# ProProject_PetCareSTM32_MiniSTM32_2024-0.net
KiCad netlist of a schematic drawn in EasyEDA Pro
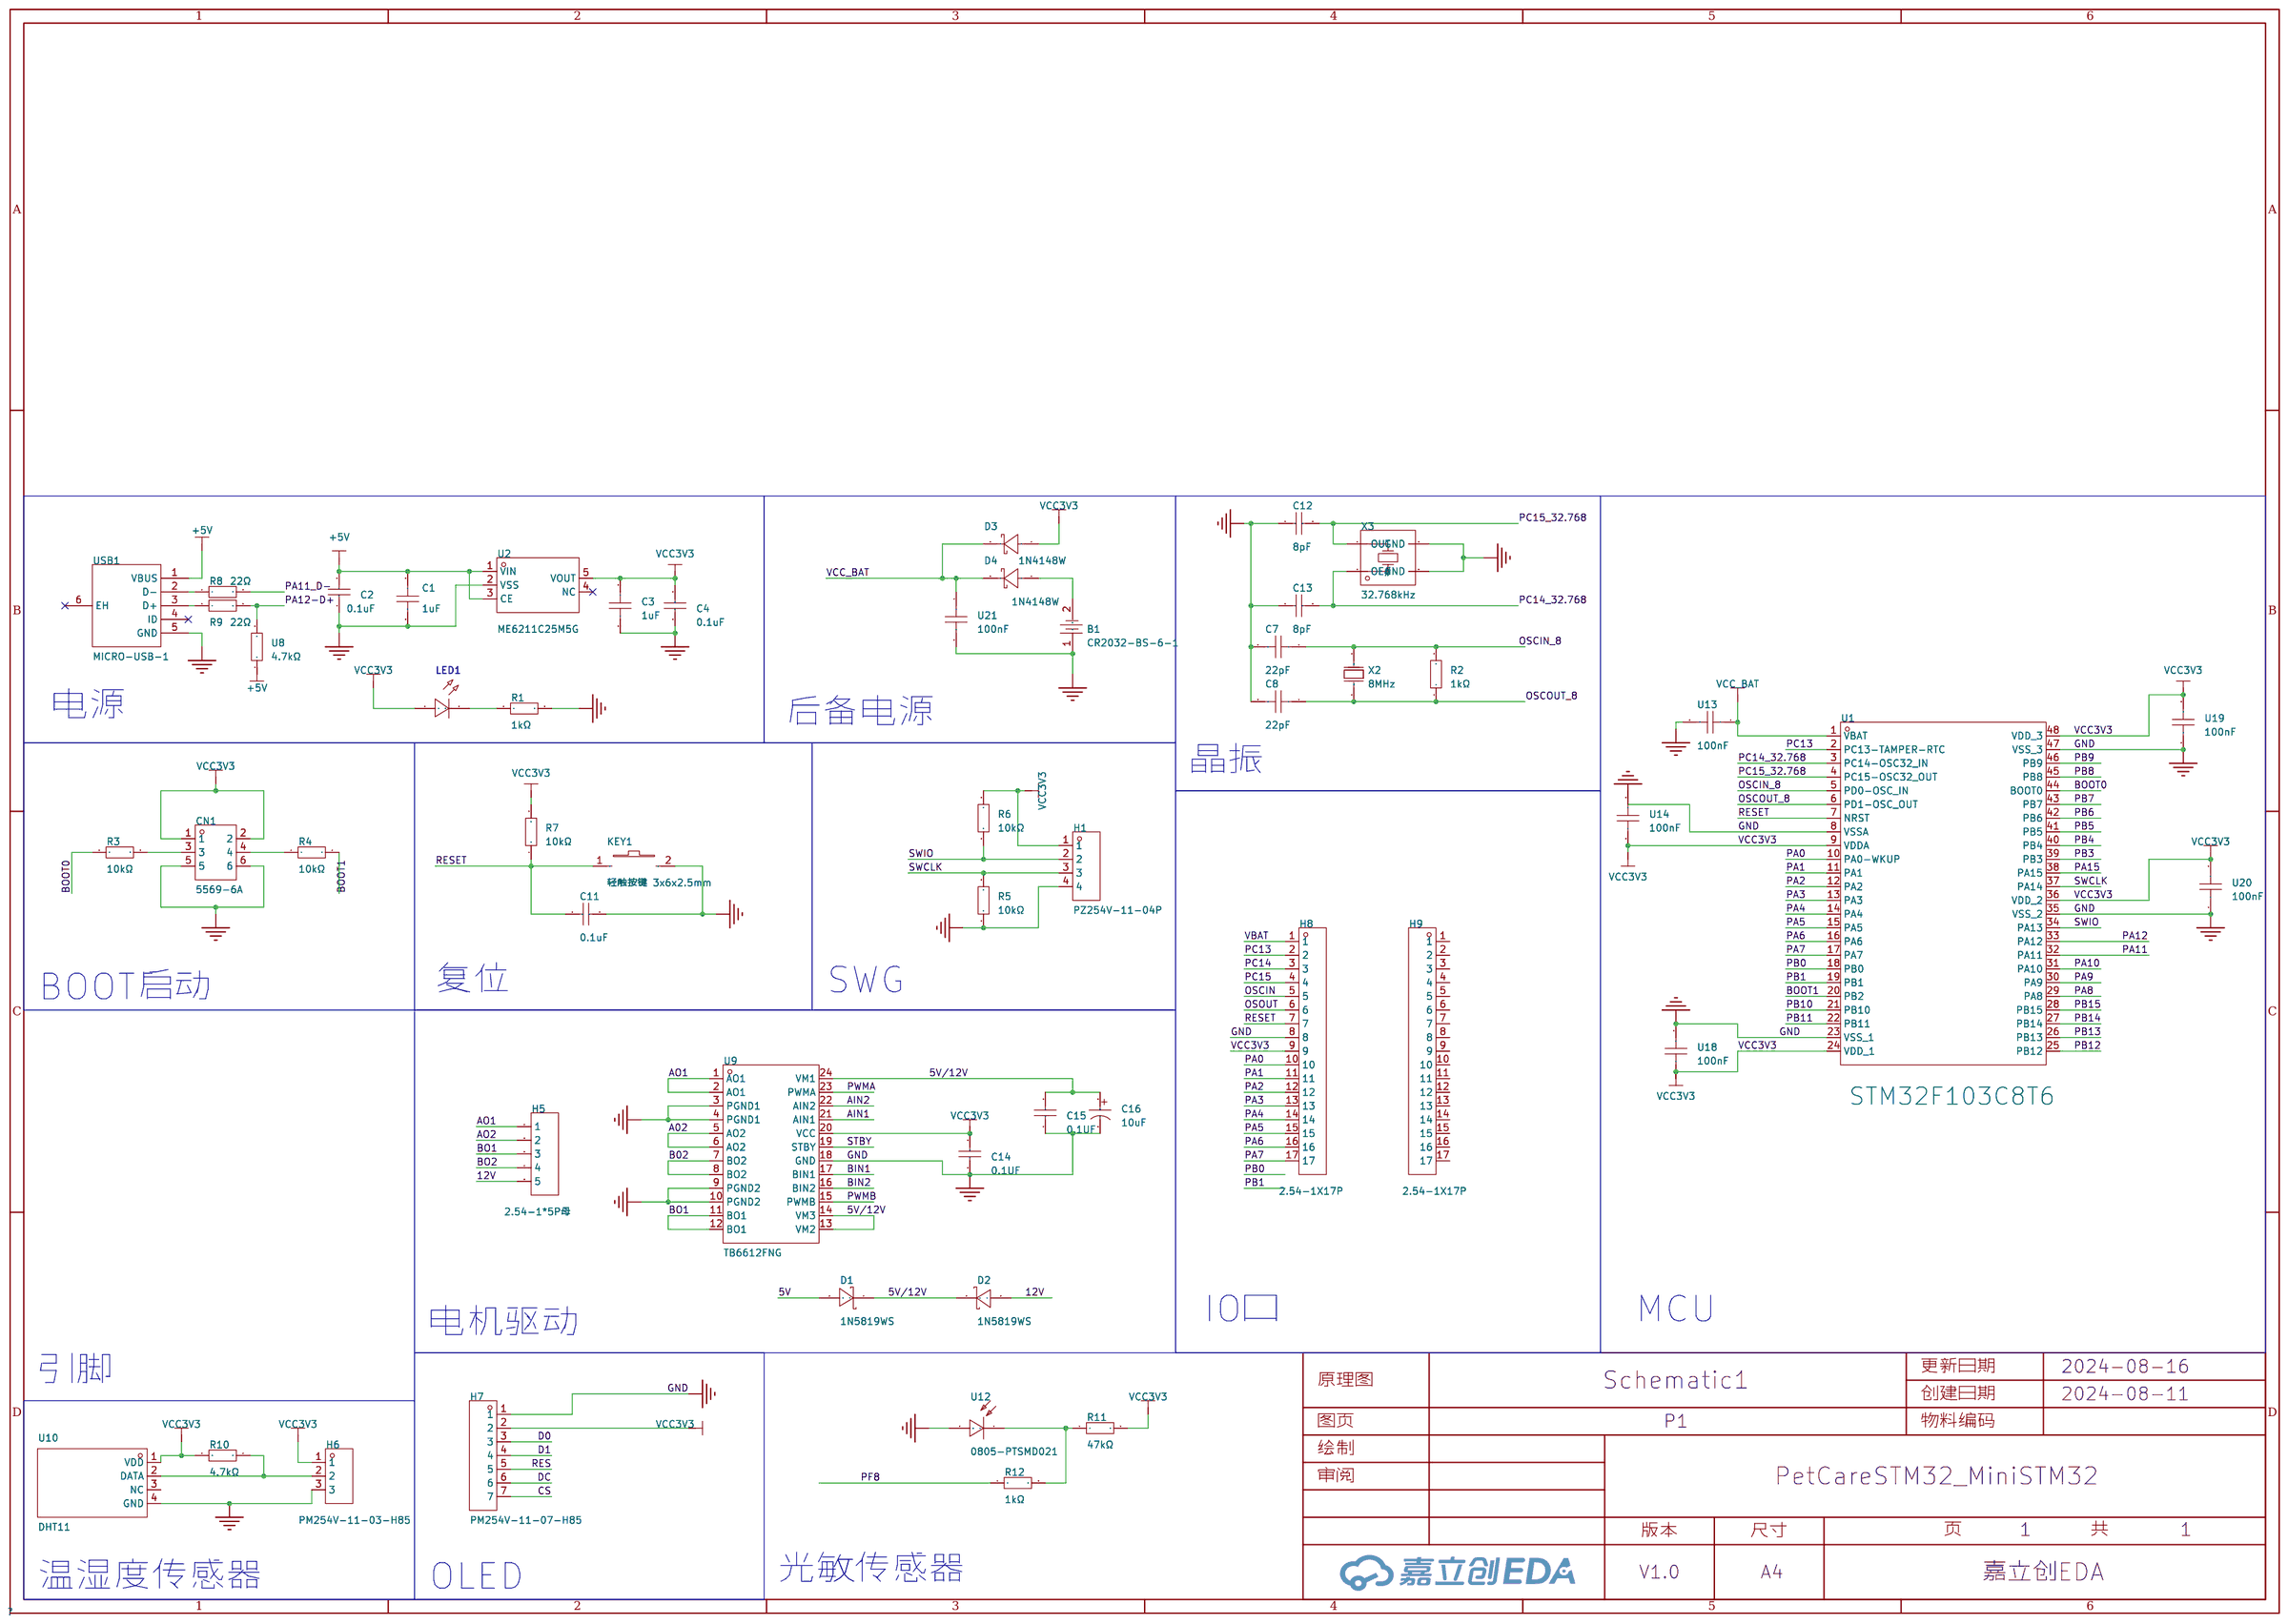
[diagram p0: schematic sheet]

(export (version "E")
  (design (tool "Eeschema 10.0.6"))
  (components
    (comp (ref "B1")
      (value "CR2032-BS-6-1")
      (footprint "easyedapro:BAT-TH_CR2032-BS-6-1")
      (description "连接器类型:电池底座;适用电池规格:CR2032;工作温度范围:-;")
      (fields (field (name "Manufacturer") "Q&J"))
      (libsource (lib "easyedapro") (part "CR2032-BS-6-1"))
    )
    (comp (ref "C1")
      (value "1uF")
      (footprint "easyedapro:C0603")
      (description "容值:1uF;精度:±10%;额定电压:50V;材质(温度系数):X5R;")
      (fields
        (field (name "Manufacturer Part") "CL10A105KB8NNNC")
        (field (name "Manufacturer") "SAMSUNG(三星)")
      )
      (libsource (lib "easyedapro") (part "CL10A105KB8NNNC"))
    )
    (comp (ref "C2")
      (value "0.1uF")
      (footprint "easyedapro:C0603")
      (libsource (lib "easyedapro") (part "CAPCER0.1UF16VX5R0603,CAPCER0.1UF25VX5R0603,CAPCER0.1UF16VX7R0603"))
    )
    (comp (ref "C3")
      (value "1uF")
      (footprint "easyedapro:C0603")
      (description "容值:1uF;精度:±10%;额定电压:50V;材质(温度系数):X5R;")
      (fields
        (field (name "Manufacturer Part") "CL10A105KB8NNNC")
        (field (name "Manufacturer") "SAMSUNG(三星)")
      )
      (libsource (lib "easyedapro") (part "CL10A105KB8NNNC"))
    )
    (comp (ref "C4")
      (value "0.1uF")
      (footprint "easyedapro:C0603")
      (libsource (lib "easyedapro") (part "CAPCER0.1UF16VX5R0603,CAPCER0.1UF25VX5R0603,CAPCER0.1UF16VX7R0603"))
    )
    (comp (ref "C7")
      (value "22pF")
      (footprint "easyedapro:C0603")
      (description "容值:22pF;精度:±5%;额定电压:50V;材质(温度系数):C0G;")
      (fields
        (field (name "Manufacturer Part") "CL10C220JB81PNC")
        (field (name "Manufacturer") "SAMSUNG(三星)")
      )
      (libsource (lib "easyedapro") (part "CL10C220JB81PNC"))
    )
    (comp (ref "C8")
      (value "22pF")
      (footprint "easyedapro:C0603")
      (description "容值:22pF;精度:±5%;额定电压:50V;材质(温度系数):C0G;")
      (fields
        (field (name "Manufacturer Part") "CL10C220JB81PNC")
        (field (name "Manufacturer") "SAMSUNG(三星)")
      )
      (libsource (lib "easyedapro") (part "CL10C220JB81PNC"))
    )
    (comp (ref "C11")
      (value "0.1uF")
      (footprint "easyedapro:C0603")
      (libsource (lib "easyedapro") (part "CAPCER0.1UF16VX5R0603,CAPCER0.1UF25VX5R0603,CAPCER0.1UF16VX7R0603"))
    )
    (comp (ref "C12")
      (value "8pF")
      (footprint "easyedapro:C0603")
      (description "容值:8pF;额定电压:50V;材质(温度系数):C0G;")
      (fields (field (name "Manufacturer Part") "0603CG8R0C500NT") (field (name "Manufacturer") "FH(风华)"))
      (libsource (lib "easyedapro") (part "0603CG8R0C500NT_C36508"))
    )
    (comp (ref "C13")
      (value "8pF")
      (footprint "easyedapro:C0603")
      (description "容值:8pF;额定电压:50V;材质(温度系数):C0G;")
      (fields (field (name "Manufacturer Part") "0603CG8R0C500NT") (field (name "Manufacturer") "FH(风华)"))
      (libsource (lib "easyedapro") (part "0603CG8R0C500NT_C36508"))
    )
    (comp (ref "C14")
      (value "0.1UF")
      (footprint "easyedapro:C0603")
      (libsource (lib "easyedapro") (part "CAPCER0.1UF16VX5R0603,CAPCER0.1UF25VX5R0603,CAPCER0.1UF16VX7R0603"))
    )
    (comp (ref "C15")
      (value "0.1UF")
      (footprint "easyedapro:C0603")
      (libsource (lib "easyedapro") (part "CAPCER0.1UF16VX5R0603,CAPCER0.1UF25VX5R0603,CAPCER0.1UF16VX7R0603"))
    )
    (comp (ref "C16")
      (value "10uF")
      (footprint "easyedapro:CAP-TH_BD5.0-P2.00-D0.8-FD")
      (description "容值:10uF;精度:±20%;额定电压:25V;")
      (fields (field (name "Manufacturer Part") "KF100M025C110A") (field (name "Manufacturer") "CapXon(丰宾)"))
      (libsource (lib "easyedapro") (part "KF100M025C110A"))
    )
    (comp (ref "CN1")
      (value "5569-6A")
      (footprint "easyedapro:CONN-TH_6P-P4.20_5569-6A-1")
      (libsource (lib "easyedapro") (part "5569-6A"))
    )
    (comp (ref "D1")
      (value "1N5819WS")
      (footprint "easyedapro:SOD-323_L1.8-W1.3-LS2.5-RD")
      (description "正向压降(Vf):600mV@1A;直流反向耐压(Vr):40V;平均整流电流(Io):1A;")
      (fields (field (name "Manufacturer") "Hottech(合科泰)"))
      (libsource (lib "easyedapro") (part "1N5819WS"))
    )
    (comp (ref "D2")
      (value "1N5819WS")
      (footprint "easyedapro:SOD-323_L1.8-W1.3-LS2.5-RD")
      (description "正向压降(Vf):600mV@1A;直流反向耐压(Vr):40V;平均整流电流(Io):1A;")
      (fields (field (name "Manufacturer") "Hottech(合科泰)"))
      (libsource (lib "easyedapro") (part "1N5819WS"))
    )
    (comp (ref "D3")
      (value "1N4148W")
      (footprint "easyedapro:SOD-123_L2.7-W1.6-LS3.7-FD")
      (description "二极管配置:独立式;正向压降(Vf):1.25V@150mA;直流反向耐压(Vr):100V;平均整流电流(Io):150mA;功率:400mW;反向恢复时间(trr):4ns;")
      (fields (field (name "Manufacturer") "宏迦橙"))
      (libsource (lib "easyedapro") (part "1N4148W_C7420318"))
    )
    (comp (ref "D4")
      (value "1N4148W")
      (footprint "easyedapro:SOD-123_L2.7-W1.6-LS3.7-FD")
      (description "二极管配置:独立式;正向压降(Vf):1.25V@150mA;直流反向耐压(Vr):100V;平均整流电流(Io):150mA;功率:400mW;反向恢复时间(trr):4ns;")
      (fields (field (name "Manufacturer") "宏迦橙"))
      (libsource (lib "easyedapro") (part "1N4148W_C7420318"))
    )
    (comp (ref "H1")
      (value "PZ254V-11-04P")
      (footprint "easyedapro:HDR-TH_4P-P2.54-V-M")
      (fields (field (name "Manufacturer") "XFCN(兴飞)"))
      (libsource (lib "easyedapro") (part "PZ254V-11-04P_C2691448"))
    )
    (comp (ref "H5")
      (value "2.54-1*5P母")
      (footprint "easyedapro:HDR-TH_5P-P2.54-V-F")
      (description "插孔结构:1x5P;间距:2.54mm;行距:-;安装类型:直插;排数:单排;总孔位数:5P;塑高:-;触头材质:-;触头镀层:-;")
      (fields (field (name "Manufacturer") "BOOMELE(博穆精密)"))
      (libsource (lib "easyedapro") (part "Header-Female-2.54_1x5"))
    )
    (comp (ref "H6")
      (value "PM254V-11-03-H85")
      (footprint "easyedapro:HDR-TH_3P-P2.54-V-F")
      (description "插孔结构:1x3P;间距:2.54mm;行距:-;安装类型:直插;排数:单排;总孔位数:3P;塑高:-;触头材质:黄铜;触头镀层:-;")
      (fields (field (name "Manufacturer") "XFCN(兴飞)"))
      (libsource (lib "easyedapro") (part "PM254V-11-03-H85"))
    )
    (comp (ref "H7")
      (value "PM254V-11-07-H85")
      (footprint "easyedapro:HDR-TH_7P-P2.54-V-F")
      (fields (field (name "Manufacturer") "XFCN(兴飞)"))
      (libsource (lib "easyedapro") (part "PM254V-11-07-H85"))
    )
    (comp (ref "H8")
      (value "2.54-1X17P")
      (footprint "easyedapro:HDR-TH_17P-P2.54-V-M")
      (fields (field (name "Manufacturer") "kinghelm(金航标)"))
      (libsource (lib "easyedapro") (part "KH-2.54PH180-1X17P-L11.5"))
    )
    (comp (ref "H9")
      (value "2.54-1X17P")
      (footprint "easyedapro:HDR-TH_17P-P2.54-V-M")
      (fields (field (name "Manufacturer") "kinghelm(金航标)"))
      (libsource (lib "easyedapro") (part "KH-2.54PH180-1X17P-L11.5"))
    )
    (comp (ref "KEY1")
      (value "轻触按键 3x6x2.5mm")
      (footprint "easyedapro:SW-SMD_L6.0-W3.6-LS8.0")
      (libsource (lib "easyedapro") (part "3x6x2.5mm"))
    )
    (comp (ref "LED1")
      (value "~")
      (footprint "easyedapro:LED_0805")
      (libsource (lib "easyedapro") (part "LED_B"))
    )
    (comp (ref "R1")
      (value "1kΩ")
      (footprint "easyedapro:R0603")
      (description "电阻类型:厚膜电阻;阻值:1kΩ;精度:±1%;功率:100mW;最大工作电压:75V;温度系数:±100ppm/°C;")
      (fields (field (name "Manufacturer Part") "RC0603FR-071KL") (field (name "Manufacturer") "YAGEO(国巨)"))
      (libsource (lib "easyedapro") (part "RC0603FR-071KL"))
    )
    (comp (ref "R2")
      (value "1kΩ")
      (footprint "easyedapro:R0603")
      (description "电阻类型:厚膜电阻;阻值:1kΩ;精度:±0.5%;功率:100mW;最大工作电压:75V;温度系数:±100ppm/°C;")
      (fields
        (field (name "Manufacturer Part") "0603WAD1001T5E")
        (field (name "Manufacturer") "UNI-ROYAL(厚声)")
      )
      (libsource (lib "easyedapro") (part "0603WAD1001T5E"))
    )
    (comp (ref "R3")
      (value "10kΩ")
      (footprint "easyedapro:R0603")
      (description "电阻类型:厚膜电阻;阻值:10kΩ;精度:±1%;功率:100mW;最大工作电压:75V;温度系数:±100ppm/°C;")
      (fields
        (field (name "Manufacturer Part") "0603WAF1002T5E")
        (field (name "Manufacturer") "UNI-ROYAL(厚声)")
      )
      (libsource (lib "easyedapro") (part "0603WAF1002T5E"))
    )
    (comp (ref "R4")
      (value "10kΩ")
      (footprint "easyedapro:R0603")
      (description "电阻类型:厚膜电阻;阻值:10kΩ;精度:±1%;功率:100mW;最大工作电压:75V;温度系数:±100ppm/°C;")
      (fields
        (field (name "Manufacturer Part") "0603WAF1002T5E")
        (field (name "Manufacturer") "UNI-ROYAL(厚声)")
      )
      (libsource (lib "easyedapro") (part "0603WAF1002T5E"))
    )
    (comp (ref "R5")
      (value "10kΩ")
      (footprint "easyedapro:R0603")
      (description "电阻类型:厚膜电阻;阻值:10kΩ;精度:±1%;功率:100mW;最大工作电压:75V;温度系数:±100ppm/°C;")
      (fields
        (field (name "Manufacturer Part") "0603WAF1002T5E")
        (field (name "Manufacturer") "UNI-ROYAL(厚声)")
      )
      (libsource (lib "easyedapro") (part "0603WAF1002T5E"))
    )
    (comp (ref "R6")
      (value "10kΩ")
      (footprint "easyedapro:R0603")
      (description "电阻类型:厚膜电阻;阻值:10kΩ;精度:±1%;功率:100mW;最大工作电压:75V;温度系数:±100ppm/°C;")
      (fields
        (field (name "Manufacturer Part") "0603WAF1002T5E")
        (field (name "Manufacturer") "UNI-ROYAL(厚声)")
      )
      (libsource (lib "easyedapro") (part "0603WAF1002T5E"))
    )
    (comp (ref "R7")
      (value "10kΩ")
      (footprint "easyedapro:R0603")
      (description "电阻类型:厚膜电阻;阻值:10kΩ;精度:±1%;功率:100mW;最大工作电压:75V;温度系数:±100ppm/°C;")
      (fields
        (field (name "Manufacturer Part") "0603WAF1002T5E")
        (field (name "Manufacturer") "UNI-ROYAL(厚声)")
      )
      (libsource (lib "easyedapro") (part "0603WAF1002T5E"))
    )
    (comp (ref "R8")
      (value "22Ω")
      (footprint "easyedapro:R0805")
      (description "电阻类型:薄膜电阻;阻值:22Ω;精度:±1%;功率:250mW;最大工作电压:150V;温度系数:±25ppm/°C;")
      (fields
        (field (name "Manufacturer Part") "TC0525F220JT5E")
        (field (name "Manufacturer") "UNI-ROYAL(厚声)")
      )
      (libsource (lib "easyedapro") (part "TC0525F220JT5E"))
    )
    (comp (ref "R9")
      (value "22Ω")
      (footprint "easyedapro:R0805")
      (description "电阻类型:薄膜电阻;阻值:22Ω;精度:±1%;功率:250mW;最大工作电压:150V;温度系数:±25ppm/°C;")
      (fields
        (field (name "Manufacturer Part") "TC0525F220JT5E")
        (field (name "Manufacturer") "UNI-ROYAL(厚声)")
      )
      (libsource (lib "easyedapro") (part "TC0525F220JT5E"))
    )
    (comp (ref "R10")
      (value "4.7kΩ")
      (footprint "easyedapro:R1206")
      (description "电阻类型:厚膜电阻;阻值:4.7kΩ;精度:±1%;功率:250mW;最大工作电压:200V;温度系数:±100ppm/°C;")
      (fields
        (field (name "Manufacturer Part") "1206W4F4701T5E")
        (field (name "Manufacturer") "UNI-ROYAL(厚声)")
      )
      (libsource (lib "easyedapro") (part "1206W4F4701T5E"))
    )
    (comp (ref "R11")
      (value "47kΩ")
      (footprint "easyedapro:R0805")
      (description "电阻类型:厚膜电阻;阻值:47kΩ;精度:±1%;功率:125mW;最大工作电压:150V;温度系数:±100ppm/°C;")
      (fields
        (field (name "Manufacturer Part") "0805W8F4702T5E")
        (field (name "Manufacturer") "UNI-ROYAL(厚声)")
      )
      (libsource (lib "easyedapro") (part "0805W8F4702T5E"))
    )
    (comp (ref "R12")
      (value "1kΩ")
      (footprint "easyedapro:R0603")
      (description "电阻类型:厚膜电阻;阻值:1kΩ;精度:±1%;功率:100mW;最大工作电压:75V;温度系数:±100ppm/°C;")
      (fields (field (name "Manufacturer Part") "RC0603FR-071KL") (field (name "Manufacturer") "YAGEO(国巨)"))
      (libsource (lib "easyedapro") (part "RC0603FR-071KL"))
    )
    (comp (ref "U1")
      (value "STM32F103C8T6")
      (footprint "easyedapro:LQFP-48_L7.0-W7.0-P0.50-LS9.0-BL")
      (description "CPU内核:ARM-M3;程序存储容量:64KB;RAM总容量:20KB;GPIO端口数量:37;工作电压范围:2V~3.6V;CPU最大主频:72MHz;程序存储器类型:FLASH;")
      (fields (field (name "Manufacturer") "ST(意法半导体)"))
      (libsource (lib "easyedapro") (part "STM32F103C8T6"))
    )
    (comp (ref "U2")
      (value "ME6211C25M5G")
      (footprint "easyedapro:SOT-23-5_L2.9-W1.7-P0.95-LS2.8-BL")
      (fields (field (name "Manufacturer") "MICRONE(南京微盟)"))
      (libsource (lib "easyedapro") (part "ME6211C25M5G"))
    )
    (comp (ref "U8")
      (value "4.7kΩ")
      (footprint "easyedapro:R0603")
      (description "电阻类型:薄膜电阻;阻值:4.7kΩ;精度:±1%;功率:100mW;最大工作电压:75V;温度系数:±50ppm/°C;")
      (fields (field (name "Manufacturer Part") "AR03FTDX4701A") (field (name "Manufacturer") "Viking(光颉)"))
      (libsource (lib "easyedapro") (part "AR03FTDX4701A"))
    )
    (comp (ref "U9")
      (value "TB6612FNG")
      (footprint "easyedapro:SSOP-24_L8.4-W5.8-P0.65-LS7.8-BL")
      (description "双直流电机驱动器集成电路")
      (fields (field (name "Manufacturer") "TOSHIBA(东芝)"))
      (libsource (lib "easyedapro") (part "TB6612FNG(O,C,8,EL"))
    )
    (comp (ref "U10")
      (value "DHT11")
      (footprint "easyedapro:SENSOR-TH_DHT11")
      (description "新款电容式数字温湿度传感器,老款已停产16.1x12.6x5.8mm")
      (fields (field (name "Manufacturer") "广州奥松"))
      (libsource (lib "easyedapro") (part "DHT11"))
    )
    (comp (ref "U12")
      (value "0805-PTSMD021")
      (footprint "easyedapro:OPTO-SMD_L2.0-W1.3_RPM-075PTT86")
      (fields (field (name "Manufacturer") "JCHL(晶创和立)"))
      (libsource (lib "easyedapro") (part "0805-PTSM D021"))
    )
    (comp (ref "U13")
      (value "100nF")
      (footprint "easyedapro:C0603")
      (description "容值:100nF;精度:±10%;额定电压:50V;材质(温度系数):X7R;")
      (fields
        (field (name "Manufacturer Part") "CGA0603X7R104K500JT")
        (field (name "Manufacturer") "HRE(芯声)")
      )
      (libsource (lib "easyedapro") (part "CGA0603X7R104K500JT"))
    )
    (comp (ref "U14")
      (value "100nF")
      (footprint "easyedapro:C0603")
      (description "容值:100nF;精度:±10%;额定电压:50V;材质(温度系数):X7R;")
      (fields
        (field (name "Manufacturer Part") "CGA0603X7R104K500JT")
        (field (name "Manufacturer") "HRE(芯声)")
      )
      (libsource (lib "easyedapro") (part "CGA0603X7R104K500JT"))
    )
    (comp (ref "U18")
      (value "100nF")
      (footprint "easyedapro:C0603")
      (description "容值:100nF;精度:±10%;额定电压:50V;材质(温度系数):X7R;")
      (fields
        (field (name "Manufacturer Part") "CGA0603X7R104K500JT")
        (field (name "Manufacturer") "HRE(芯声)")
      )
      (libsource (lib "easyedapro") (part "CGA0603X7R104K500JT"))
    )
    (comp (ref "U19")
      (value "100nF")
      (footprint "easyedapro:C0603")
      (description "容值:100nF;精度:±10%;额定电压:50V;材质(温度系数):X7R;")
      (fields
        (field (name "Manufacturer Part") "CGA0603X7R104K500JT")
        (field (name "Manufacturer") "HRE(芯声)")
      )
      (libsource (lib "easyedapro") (part "CGA0603X7R104K500JT"))
    )
    (comp (ref "U20")
      (value "100nF")
      (footprint "easyedapro:C0603")
      (description "容值:100nF;精度:±10%;额定电压:50V;材质(温度系数):X7R;")
      (fields
        (field (name "Manufacturer Part") "CGA0603X7R104K500JT")
        (field (name "Manufacturer") "HRE(芯声)")
      )
      (libsource (lib "easyedapro") (part "CGA0603X7R104K500JT"))
    )
    (comp (ref "U21")
      (value "100nF")
      (footprint "easyedapro:C0603")
      (description "容值:100nF;精度:±10%;额定电压:50V;材质(温度系数):X7R;")
      (fields
        (field (name "Manufacturer Part") "CGA0603X7R104K500JT")
        (field (name "Manufacturer") "HRE(芯声)")
      )
      (libsource (lib "easyedapro") (part "CGA0603X7R104K500JT"))
    )
    (comp (ref "USB1")
      (value "MICRO-USB-1")
      (footprint "easyedapro:MICRO-USB-SMD_C9900008946")
      (libsource (lib "easyedapro") (part "MICRO-USB-1"))
    )
    (comp (ref "X2")
      (value "8MHz")
      (footprint "easyedapro:OSC-SMD_L5.0-W3.2")
      (description "晶振类型:贴片晶振;频率:8MHz;常温频差:±20ppm;外接负载电容:18pF;频率稳定度(全温):±30ppm;")
      (fields
        (field (name "Manufacturer Part") "ABM3-8.000MHZ-D2Y-T")
        (field (name "Manufacturer") "ABRACON")
      )
      (libsource (lib "easyedapro") (part "ABM3-8.000MHZ-D2Y-T"))
    )
    (comp (ref "X3")
      (value "32.768kHz")
      (footprint "easyedapro:CRYSTAL-SMD_4P-L8.0-W3.8-BL")
      (description "晶振类型:-;频率:32.768kHz;常温频差:±20ppm;外接负载电容:12.5pF;频率稳定度(全温):-;")
      (fields (field (name "Manufacturer Part") "ABS25-32.768KHZ-T") (field (name "Manufacturer") "ABRACON"))
      (libsource (lib "easyedapro") (part "ABS25-32.768KHZ-T"))
    )
  )
  (nets
    (net (code "1") (name "+5V") (class "Default")
      (node (ref "C1") (pin "2") (pinfunction "2_2") (pintype "unspecified"))
      (node (ref "C2") (pin "2") (pinfunction "2_2") (pintype "input"))
      (node (ref "U2") (pin "1") (pinfunction "VIN_1") (pintype "unspecified"))
      (node (ref "U2") (pin "3") (pinfunction "CE_3") (pintype "unspecified"))
      (node (ref "U8") (pin "1") (pinfunction "1_1") (pintype "unspecified"))
      (node (ref "USB1") (pin "1") (pinfunction "VBUS_1") (pintype "input"))
    )
    (net (code "2") (name "/5V") (class "Default")
      (node (ref "D1") (pin "2") (pinfunction "A_2") (pintype "unspecified"))
    )
    (net (code "3") (name "/5V{slash}12V") (class "Default")
      (node (ref "C15") (pin "2") (pinfunction "2_2") (pintype "input"))
      (node (ref "C16") (pin "1") (pinfunction "1_1") (pintype "input"))
      (node (ref "D1") (pin "1") (pinfunction "K_1") (pintype "unspecified"))
      (node (ref "D2") (pin "1") (pinfunction "K_1") (pintype "unspecified"))
      (node (ref "U9") (pin "13") (pinfunction "VM2_13") (pintype "unspecified"))
      (node (ref "U9") (pin "14") (pinfunction "VM3_14") (pintype "unspecified"))
      (node (ref "U9") (pin "24") (pinfunction "VM1_24") (pintype "unspecified"))
    )
    (net (code "4") (name "/12V") (class "Default")
      (node (ref "D2") (pin "2") (pinfunction "A_2") (pintype "unspecified"))
      (node (ref "H5") (pin "5") (pinfunction "5_5") (pintype "input"))
    )
    (net (code "5") (name "/A02") (class "Default")
      (node (ref "U9") (pin "5") (pinfunction "AO2_5") (pintype "unspecified"))
      (node (ref "U9") (pin "6") (pinfunction "AO2_6") (pintype "unspecified"))
    )
    (net (code "6") (name "/AIN1") (class "Default")
      (node (ref "U9") (pin "21") (pinfunction "AIN1_21") (pintype "unspecified"))
    )
    (net (code "7") (name "/AIN2") (class "Default")
      (node (ref "U9") (pin "22") (pinfunction "AIN2_22") (pintype "unspecified"))
    )
    (net (code "8") (name "/AO1") (class "Default")
      (node (ref "H5") (pin "1") (pinfunction "1_1") (pintype "input"))
      (node (ref "U9") (pin "1") (pinfunction "AO1_1") (pintype "unspecified"))
      (node (ref "U9") (pin "2") (pinfunction "AO1_2") (pintype "unspecified"))
    )
    (net (code "9") (name "/AO2") (class "Default")
      (node (ref "H5") (pin "2") (pinfunction "2_2") (pintype "input"))
    )
    (net (code "10") (name "/B02") (class "Default")
      (node (ref "U9") (pin "7") (pinfunction "BO2_7") (pintype "unspecified"))
      (node (ref "U9") (pin "8") (pinfunction "BO2_8") (pintype "unspecified"))
    )
    (net (code "11") (name "/BIN1") (class "Default")
      (node (ref "U9") (pin "17") (pinfunction "BIN1_17") (pintype "unspecified"))
    )
    (net (code "12") (name "/BIN2") (class "Default")
      (node (ref "U9") (pin "16") (pinfunction "BIN2_16") (pintype "unspecified"))
    )
    (net (code "13") (name "/BO1") (class "Default")
      (node (ref "H5") (pin "3") (pinfunction "3_3") (pintype "input"))
      (node (ref "U9") (pin "11") (pinfunction "BO1_11") (pintype "unspecified"))
      (node (ref "U9") (pin "12") (pinfunction "BO1_12") (pintype "unspecified"))
    )
    (net (code "14") (name "/BO2") (class "Default")
      (node (ref "H5") (pin "4") (pinfunction "4_4") (pintype "input"))
    )
    (net (code "15") (name "/BOOT0") (class "Default")
      (node (ref "R3") (pin "1") (pinfunction "1_1") (pintype "input"))
      (node (ref "U1") (pin "44") (pinfunction "BOOT0_44") (pintype "unspecified"))
    )
    (net (code "16") (name "/BOOT1") (class "Default")
      (node (ref "R4") (pin "2") (pinfunction "2_2") (pintype "input"))
      (node (ref "U1") (pin "20") (pinfunction "PB2_20") (pintype "unspecified"))
    )
    (net (code "17") (name "/CS") (class "Default")
      (node (ref "H7") (pin "7") (pinfunction "7_7") (pintype "unspecified"))
    )
    (net (code "18") (name "/D0") (class "Default")
      (node (ref "H7") (pin "3") (pinfunction "3_3") (pintype "unspecified"))
    )
    (net (code "19") (name "/D1") (class "Default")
      (node (ref "H7") (pin "4") (pinfunction "4_4") (pintype "unspecified"))
    )
    (net (code "20") (name "/DC") (class "Default")
      (node (ref "H7") (pin "6") (pinfunction "6_6") (pintype "unspecified"))
    )
    (net (code "21") (name "/OSCIN") (class "Default")
      (node (ref "H8") (pin "5") (pinfunction "5_5") (pintype "unspecified"))
    )
    (net (code "22") (name "/OSCIN_8") (class "Default")
      (node (ref "C7") (pin "1") (pinfunction "1_1") (pintype "unspecified"))
      (node (ref "R2") (pin "2") (pinfunction "2_2") (pintype "input"))
      (node (ref "U1") (pin "5") (pinfunction "PD0-OSC_IN_5") (pintype "unspecified"))
      (node (ref "X2") (pin "2") (pinfunction "OSC2_2") (pintype "input"))
    )
    (net (code "23") (name "/OSCOUT_8") (class "Default")
      (node (ref "C8") (pin "1") (pinfunction "1_1") (pintype "unspecified"))
      (node (ref "R2") (pin "1") (pinfunction "1_1") (pintype "input"))
      (node (ref "U1") (pin "6") (pinfunction "PD1-OSC_OUT_6") (pintype "unspecified"))
      (node (ref "X2") (pin "1") (pinfunction "OSC1_1") (pintype "input"))
    )
    (net (code "24") (name "/OSOUT") (class "Default")
      (node (ref "H8") (pin "6") (pinfunction "6_6") (pintype "unspecified"))
    )
    (net (code "25") (name "/PA0") (class "Default")
      (node (ref "H8") (pin "10") (pinfunction "10_10") (pintype "unspecified"))
      (node (ref "U1") (pin "10") (pinfunction "PA0-WKUP_10") (pintype "unspecified"))
    )
    (net (code "26") (name "/PA1") (class "Default")
      (node (ref "H8") (pin "11") (pinfunction "11_11") (pintype "unspecified"))
      (node (ref "U1") (pin "11") (pinfunction "PA1_11") (pintype "unspecified"))
    )
    (net (code "27") (name "/PA2") (class "Default")
      (node (ref "H8") (pin "12") (pinfunction "12_12") (pintype "unspecified"))
      (node (ref "U1") (pin "12") (pinfunction "PA2_12") (pintype "unspecified"))
    )
    (net (code "28") (name "/PA3") (class "Default")
      (node (ref "H8") (pin "13") (pinfunction "13_13") (pintype "unspecified"))
      (node (ref "U1") (pin "13") (pinfunction "PA3_13") (pintype "unspecified"))
    )
    (net (code "29") (name "/PA4") (class "Default")
      (node (ref "H8") (pin "14") (pinfunction "14_14") (pintype "unspecified"))
      (node (ref "U1") (pin "14") (pinfunction "PA4_14") (pintype "unspecified"))
    )
    (net (code "30") (name "/PA5") (class "Default")
      (node (ref "H8") (pin "15") (pinfunction "15_15") (pintype "unspecified"))
      (node (ref "U1") (pin "15") (pinfunction "PA5_15") (pintype "unspecified"))
    )
    (net (code "31") (name "/PA6") (class "Default")
      (node (ref "H8") (pin "16") (pinfunction "16_16") (pintype "unspecified"))
      (node (ref "U1") (pin "16") (pinfunction "PA6_16") (pintype "unspecified"))
    )
    (net (code "32") (name "/PA7") (class "Default")
      (node (ref "H8") (pin "17") (pinfunction "17_17") (pintype "unspecified"))
      (node (ref "U1") (pin "17") (pinfunction "PA7_17") (pintype "unspecified"))
    )
    (net (code "33") (name "/PA8") (class "Default")
      (node (ref "U1") (pin "29") (pinfunction "PA8_29") (pintype "unspecified"))
    )
    (net (code "34") (name "/PA9") (class "Default")
      (node (ref "U1") (pin "30") (pinfunction "PA9_30") (pintype "unspecified"))
    )
    (net (code "35") (name "/PA10") (class "Default")
      (node (ref "U1") (pin "31") (pinfunction "PA10_31") (pintype "unspecified"))
    )
    (net (code "36") (name "/PA11") (class "Default")
      (node (ref "U1") (pin "32") (pinfunction "PA11_32") (pintype "unspecified"))
    )
    (net (code "37") (name "/PA11_D-") (class "Default")
      (node (ref "R8") (pin "2") (pinfunction "2_2") (pintype "input"))
    )
    (net (code "38") (name "/PA12") (class "Default")
      (node (ref "U1") (pin "33") (pinfunction "PA12_33") (pintype "unspecified"))
    )
    (net (code "39") (name "/PA12-D+") (class "Default")
      (node (ref "R9") (pin "2") (pinfunction "2_2") (pintype "input"))
      (node (ref "U8") (pin "2") (pinfunction "2_2") (pintype "unspecified"))
    )
    (net (code "40") (name "/PA15") (class "Default")
      (node (ref "U1") (pin "38") (pinfunction "PA15_38") (pintype "unspecified"))
    )
    (net (code "41") (name "/PB0") (class "Default")
      (node (ref "U1") (pin "18") (pinfunction "PB0_18") (pintype "unspecified"))
    )
    (net (code "42") (name "/PB1") (class "Default")
      (node (ref "U1") (pin "19") (pinfunction "PB1_19") (pintype "unspecified"))
    )
    (net (code "43") (name "/PB3") (class "Default")
      (node (ref "U1") (pin "39") (pinfunction "PB3_39") (pintype "unspecified"))
    )
    (net (code "44") (name "/PB4") (class "Default")
      (node (ref "U1") (pin "40") (pinfunction "PB4_40") (pintype "unspecified"))
    )
    (net (code "45") (name "/PB5") (class "Default")
      (node (ref "U1") (pin "41") (pinfunction "PB5_41") (pintype "unspecified"))
    )
    (net (code "46") (name "/PB6") (class "Default")
      (node (ref "U1") (pin "42") (pinfunction "PB6_42") (pintype "unspecified"))
    )
    (net (code "47") (name "/PB7") (class "Default")
      (node (ref "U1") (pin "43") (pinfunction "PB7_43") (pintype "unspecified"))
    )
    (net (code "48") (name "/PB8") (class "Default")
      (node (ref "U1") (pin "45") (pinfunction "PB8_45") (pintype "unspecified"))
    )
    (net (code "49") (name "/PB9") (class "Default")
      (node (ref "U1") (pin "46") (pinfunction "PB9_46") (pintype "unspecified"))
    )
    (net (code "50") (name "/PB10") (class "Default")
      (node (ref "U1") (pin "21") (pinfunction "PB10_21") (pintype "unspecified"))
    )
    (net (code "51") (name "/PB11") (class "Default")
      (node (ref "U1") (pin "22") (pinfunction "PB11_22") (pintype "unspecified"))
    )
    (net (code "52") (name "/PB12") (class "Default")
      (node (ref "U1") (pin "25") (pinfunction "PB12_25") (pintype "unspecified"))
    )
    (net (code "53") (name "/PB13") (class "Default")
      (node (ref "U1") (pin "26") (pinfunction "PB13_26") (pintype "unspecified"))
    )
    (net (code "54") (name "/PB14") (class "Default")
      (node (ref "U1") (pin "27") (pinfunction "PB14_27") (pintype "unspecified"))
    )
    (net (code "55") (name "/PB15") (class "Default")
      (node (ref "U1") (pin "28") (pinfunction "PB15_28") (pintype "unspecified"))
    )
    (net (code "56") (name "/PC13") (class "Default")
      (node (ref "H8") (pin "2") (pinfunction "2_2") (pintype "unspecified"))
      (node (ref "U1") (pin "2") (pinfunction "PC13-TAMPER-RTC_2") (pintype "unspecified"))
    )
    (net (code "57") (name "/PC14") (class "Default")
      (node (ref "H8") (pin "3") (pinfunction "3_3") (pintype "unspecified"))
    )
    (net (code "58") (name "/PC14_32.768") (class "Default")
      (node (ref "C13") (pin "2") (pinfunction "2_2") (pintype "input"))
      (node (ref "U1") (pin "3") (pinfunction "PC14-OSC32_IN_3") (pintype "unspecified"))
      (node (ref "X3") (pin "1") (pinfunction "OE#_1") (pintype "input"))
    )
    (net (code "59") (name "/PC15") (class "Default")
      (node (ref "H8") (pin "4") (pinfunction "4_4") (pintype "unspecified"))
    )
    (net (code "60") (name "/PC15_32.768") (class "Default")
      (node (ref "C12") (pin "2") (pinfunction "2_2") (pintype "input"))
      (node (ref "U1") (pin "4") (pinfunction "PC15-OSC32_OUT_4") (pintype "unspecified"))
      (node (ref "X3") (pin "4") (pinfunction "OUT_4") (pintype "input"))
    )
    (net (code "61") (name "/PF8") (class "Default")
      (node (ref "R12") (pin "1") (pinfunction "1_1") (pintype "input"))
    )
    (net (code "62") (name "/PWMA") (class "Default")
      (node (ref "U9") (pin "23") (pinfunction "PWMA_23") (pintype "unspecified"))
    )
    (net (code "63") (name "/PWMB") (class "Default")
      (node (ref "U9") (pin "15") (pinfunction "PWMB_15") (pintype "unspecified"))
    )
    (net (code "64") (name "/RES") (class "Default")
      (node (ref "H7") (pin "5") (pinfunction "5_5") (pintype "unspecified"))
    )
    (net (code "65") (name "/RESET") (class "Default")
      (node (ref "C11") (pin "1") (pinfunction "1_1") (pintype "input"))
      (node (ref "H8") (pin "7") (pinfunction "7_7") (pintype "unspecified"))
      (node (ref "KEY1") (pin "1") (pinfunction "1_1") (pintype "input"))
      (node (ref "R7") (pin "1") (pinfunction "1_1") (pintype "input"))
      (node (ref "U1") (pin "7") (pinfunction "NRST_7") (pintype "unspecified"))
    )
    (net (code "66") (name "/STBY") (class "Default")
      (node (ref "U9") (pin "19") (pinfunction "STBY_19") (pintype "unspecified"))
    )
    (net (code "67") (name "/SWCLK") (class "Default")
      (node (ref "H1") (pin "3") (pinfunction "3_3") (pintype "unspecified"))
      (node (ref "R5") (pin "2") (pinfunction "2_2") (pintype "input"))
      (node (ref "U1") (pin "37") (pinfunction "PA14_37") (pintype "unspecified"))
    )
    (net (code "68") (name "/SWIO") (class "Default")
      (node (ref "H1") (pin "2") (pinfunction "2_2") (pintype "unspecified"))
      (node (ref "R6") (pin "1") (pinfunction "1_1") (pintype "input"))
      (node (ref "U1") (pin "34") (pinfunction "PA13_34") (pintype "unspecified"))
    )
    (net (code "69") (name "/VBAT") (class "Default")
      (node (ref "H8") (pin "1") (pinfunction "1_1") (pintype "unspecified"))
    )
    (net (code "70") (name "GND") (class "Default")
      (node (ref "B1") (pin "1") (pinfunction "1_1") (pintype "input"))
      (node (ref "C1") (pin "1") (pinfunction "1_1") (pintype "unspecified"))
      (node (ref "C11") (pin "2") (pinfunction "2_2") (pintype "input"))
      (node (ref "C12") (pin "1") (pinfunction "1_1") (pintype "input"))
      (node (ref "C13") (pin "1") (pinfunction "1_1") (pintype "input"))
      (node (ref "C14") (pin "1") (pinfunction "1_1") (pintype "input"))
      (node (ref "C15") (pin "1") (pinfunction "1_1") (pintype "input"))
      (node (ref "C16") (pin "2") (pinfunction "2_2") (pintype "input"))
      (node (ref "C2") (pin "1") (pinfunction "1_1") (pintype "input"))
      (node (ref "C3") (pin "1") (pinfunction "1_1") (pintype "unspecified"))
      (node (ref "C4") (pin "1") (pinfunction "1_1") (pintype "input"))
      (node (ref "C7") (pin "2") (pinfunction "2_2") (pintype "unspecified"))
      (node (ref "C8") (pin "2") (pinfunction "2_2") (pintype "unspecified"))
      (node (ref "CN1") (pin "5") (pinfunction "5_5") (pintype "unspecified"))
      (node (ref "CN1") (pin "6") (pinfunction "6_6") (pintype "unspecified"))
      (node (ref "H1") (pin "4") (pinfunction "4_4") (pintype "unspecified"))
      (node (ref "H6") (pin "3") (pinfunction "3_3") (pintype "unspecified"))
      (node (ref "H7") (pin "1") (pinfunction "1_1") (pintype "unspecified"))
      (node (ref "H8") (pin "8") (pinfunction "8_8") (pintype "unspecified"))
      (node (ref "KEY1") (pin "2") (pinfunction "2_2") (pintype "input"))
      (node (ref "R1") (pin "2") (pinfunction "2_2") (pintype "input"))
      (node (ref "R5") (pin "1") (pinfunction "1_1") (pintype "input"))
      (node (ref "U1") (pin "23") (pinfunction "VSS_1_23") (pintype "unspecified"))
      (node (ref "U1") (pin "35") (pinfunction "VSS_2_35") (pintype "unspecified"))
      (node (ref "U1") (pin "47") (pinfunction "VSS_3_47") (pintype "unspecified"))
      (node (ref "U1") (pin "8") (pinfunction "VSSA_8") (pintype "unspecified"))
      (node (ref "U10") (pin "4") (pinfunction "GND_4") (pintype "unspecified"))
      (node (ref "U12") (pin "2") (pinfunction "C_2") (pintype "unspecified"))
      (node (ref "U13") (pin "2") (pinfunction "2_2") (pintype "unspecified"))
      (node (ref "U14") (pin "2") (pinfunction "2_2") (pintype "unspecified"))
      (node (ref "U18") (pin "2") (pinfunction "2_2") (pintype "unspecified"))
      (node (ref "U19") (pin "1") (pinfunction "1_1") (pintype "unspecified"))
      (node (ref "U2") (pin "2") (pinfunction "VSS_2") (pintype "unspecified"))
      (node (ref "U20") (pin "1") (pinfunction "1_1") (pintype "unspecified"))
      (node (ref "U21") (pin "2") (pinfunction "2_2") (pintype "unspecified"))
      (node (ref "U9") (pin "10") (pinfunction "PGND2_10") (pintype "unspecified"))
      (node (ref "U9") (pin "18") (pinfunction "GND_18") (pintype "unspecified"))
      (node (ref "U9") (pin "3") (pinfunction "PGND1_3") (pintype "unspecified"))
      (node (ref "U9") (pin "4") (pinfunction "PGND1_4") (pintype "unspecified"))
      (node (ref "U9") (pin "9") (pinfunction "PGND2_9") (pintype "unspecified"))
      (node (ref "USB1") (pin "5") (pinfunction "GND_5") (pintype "input"))
      (node (ref "X3") (pin "2") (pinfunction "GND_2") (pintype "input"))
      (node (ref "X3") (pin "3") (pinfunction "GND_3") (pintype "input"))
    )
    (net (code "71") (name "Net-(CN1-Pad3)") (class "Default")
      (node (ref "CN1") (pin "3") (pinfunction "3_3") (pintype "unspecified"))
      (node (ref "R3") (pin "2") (pinfunction "2_2") (pintype "input"))
    )
    (net (code "72") (name "Net-(CN1-Pad4)") (class "Default")
      (node (ref "CN1") (pin "4") (pinfunction "4_4") (pintype "unspecified"))
      (node (ref "R4") (pin "1") (pinfunction "1_1") (pintype "input"))
    )
    (net (code "73") (name "Net-(D4-A)") (class "Default")
      (node (ref "B1") (pin "2") (pinfunction "2_2") (pintype "input"))
      (node (ref "D4") (pin "1") (pinfunction "A_1") (pintype "unspecified"))
    )
    (net (code "74") (name "Net-(LED1-C)") (class "Default")
      (node (ref "LED1") (pin "1") (pinfunction "C_1") (pintype "input"))
      (node (ref "R1") (pin "1") (pinfunction "1_1") (pintype "input"))
    )
    (net (code "75") (name "Net-(U10-DATA)") (class "Default")
      (node (ref "H6") (pin "2") (pinfunction "2_2") (pintype "unspecified"))
      (node (ref "R10") (pin "1") (pinfunction "1_1") (pintype "input"))
      (node (ref "U10") (pin "2") (pinfunction "DATA_2") (pintype "unspecified"))
    )
    (net (code "76") (name "Net-(U12-E)") (class "Default")
      (node (ref "R11") (pin "1") (pinfunction "1_1") (pintype "input"))
      (node (ref "R12") (pin "2") (pinfunction "2_2") (pintype "input"))
      (node (ref "U12") (pin "1") (pinfunction "E_1") (pintype "unspecified"))
    )
    (net (code "77") (name "Net-(USB1-D+)") (class "Default")
      (node (ref "R9") (pin "1") (pinfunction "1_1") (pintype "input"))
      (node (ref "USB1") (pin "3") (pinfunction "D+_3") (pintype "input"))
    )
    (net (code "78") (name "Net-(USB1-D-)") (class "Default")
      (node (ref "R8") (pin "1") (pinfunction "1_1") (pintype "input"))
      (node (ref "USB1") (pin "2") (pinfunction "D-_2") (pintype "input"))
    )
    (net (code "79") (name "VCC3V3") (class "Default")
      (node (ref "C14") (pin "2") (pinfunction "2_2") (pintype "input"))
      (node (ref "C3") (pin "2") (pinfunction "2_2") (pintype "unspecified"))
      (node (ref "C4") (pin "2") (pinfunction "2_2") (pintype "input"))
      (node (ref "CN1") (pin "1") (pinfunction "1_1") (pintype "unspecified"))
      (node (ref "CN1") (pin "2") (pinfunction "2_2") (pintype "unspecified"))
      (node (ref "D3") (pin "1") (pinfunction "A_1") (pintype "unspecified"))
      (node (ref "H1") (pin "1") (pinfunction "1_1") (pintype "unspecified"))
      (node (ref "H6") (pin "1") (pinfunction "1_1") (pintype "unspecified"))
      (node (ref "H7") (pin "2") (pinfunction "2_2") (pintype "unspecified"))
      (node (ref "H8") (pin "9") (pinfunction "9_9") (pintype "unspecified"))
      (node (ref "LED1") (pin "2") (pinfunction "A_2") (pintype "input"))
      (node (ref "R10") (pin "2") (pinfunction "2_2") (pintype "input"))
      (node (ref "R11") (pin "2") (pinfunction "2_2") (pintype "input"))
      (node (ref "R6") (pin "2") (pinfunction "2_2") (pintype "input"))
      (node (ref "R7") (pin "2") (pinfunction "2_2") (pintype "input"))
      (node (ref "U1") (pin "24") (pinfunction "VDD_1_24") (pintype "unspecified"))
      (node (ref "U1") (pin "36") (pinfunction "VDD_2_36") (pintype "unspecified"))
      (node (ref "U1") (pin "48") (pinfunction "VDD_3_48") (pintype "unspecified"))
      (node (ref "U1") (pin "9") (pinfunction "VDDA_9") (pintype "unspecified"))
      (node (ref "U10") (pin "1") (pinfunction "VDD_1") (pintype "unspecified"))
      (node (ref "U14") (pin "1") (pinfunction "1_1") (pintype "unspecified"))
      (node (ref "U18") (pin "1") (pinfunction "1_1") (pintype "unspecified"))
      (node (ref "U19") (pin "2") (pinfunction "2_2") (pintype "unspecified"))
      (node (ref "U2") (pin "5") (pinfunction "VOUT_5") (pintype "unspecified"))
      (node (ref "U20") (pin "2") (pinfunction "2_2") (pintype "unspecified"))
      (node (ref "U9") (pin "20") (pinfunction "VCC_20") (pintype "unspecified"))
    )
    (net (code "80") (name "VCC_BAT") (class "Default")
      (node (ref "D3") (pin "2") (pinfunction "K_2") (pintype "unspecified"))
      (node (ref "D4") (pin "2") (pinfunction "K_2") (pintype "unspecified"))
      (node (ref "U1") (pin "1") (pinfunction "VBAT_1") (pintype "unspecified"))
      (node (ref "U13") (pin "1") (pinfunction "1_1") (pintype "unspecified"))
      (node (ref "U21") (pin "1") (pinfunction "1_1") (pintype "unspecified"))
    )
    (net (code "81") (name "unconnected-(H9-Pad1)") (class "Default")
      (node (ref "H9") (pin "1") (pinfunction "1_1") (pintype "unspecified"))
    )
    (net (code "82") (name "unconnected-(H9-Pad2)") (class "Default")
      (node (ref "H9") (pin "2") (pinfunction "2_2") (pintype "unspecified"))
    )
    (net (code "83") (name "unconnected-(H9-Pad3)") (class "Default")
      (node (ref "H9") (pin "3") (pinfunction "3_3") (pintype "unspecified"))
    )
    (net (code "84") (name "unconnected-(H9-Pad4)") (class "Default")
      (node (ref "H9") (pin "4") (pinfunction "4_4") (pintype "unspecified"))
    )
    (net (code "85") (name "unconnected-(H9-Pad5)") (class "Default")
      (node (ref "H9") (pin "5") (pinfunction "5_5") (pintype "unspecified"))
    )
    (net (code "86") (name "unconnected-(H9-Pad6)") (class "Default")
      (node (ref "H9") (pin "6") (pinfunction "6_6") (pintype "unspecified"))
    )
    (net (code "87") (name "unconnected-(H9-Pad7)") (class "Default")
      (node (ref "H9") (pin "7") (pinfunction "7_7") (pintype "unspecified"))
    )
    (net (code "88") (name "unconnected-(H9-Pad8)") (class "Default")
      (node (ref "H9") (pin "8") (pinfunction "8_8") (pintype "unspecified"))
    )
    (net (code "89") (name "unconnected-(H9-Pad9)") (class "Default")
      (node (ref "H9") (pin "9") (pinfunction "9_9") (pintype "unspecified"))
    )
    (net (code "90") (name "unconnected-(H9-Pad10)") (class "Default")
      (node (ref "H9") (pin "10") (pinfunction "10_10") (pintype "unspecified"))
    )
    (net (code "91") (name "unconnected-(H9-Pad11)") (class "Default")
      (node (ref "H9") (pin "11") (pinfunction "11_11") (pintype "unspecified"))
    )
    (net (code "92") (name "unconnected-(H9-Pad12)") (class "Default")
      (node (ref "H9") (pin "12") (pinfunction "12_12") (pintype "unspecified"))
    )
    (net (code "93") (name "unconnected-(H9-Pad13)") (class "Default")
      (node (ref "H9") (pin "13") (pinfunction "13_13") (pintype "unspecified"))
    )
    (net (code "94") (name "unconnected-(H9-Pad14)") (class "Default")
      (node (ref "H9") (pin "14") (pinfunction "14_14") (pintype "unspecified"))
    )
    (net (code "95") (name "unconnected-(H9-Pad15)") (class "Default")
      (node (ref "H9") (pin "15") (pinfunction "15_15") (pintype "unspecified"))
    )
    (net (code "96") (name "unconnected-(H9-Pad16)") (class "Default")
      (node (ref "H9") (pin "16") (pinfunction "16_16") (pintype "unspecified"))
    )
    (net (code "97") (name "unconnected-(H9-Pad17)") (class "Default")
      (node (ref "H9") (pin "17") (pinfunction "17_17") (pintype "unspecified"))
    )
    (net (code "98") (name "unconnected-(U2-NC-Pad4)") (class "Default")
      (node (ref "U2") (pin "4") (pinfunction "NC_4") (pintype "unspecified+no_connect"))
    )
    (net (code "99") (name "unconnected-(U10-NC-Pad3)") (class "Default")
      (node (ref "U10") (pin "3") (pinfunction "NC_3") (pintype "unspecified"))
    )
    (net (code "100") (name "unconnected-(USB1-EH-Pad6)") (class "Default")
      (node (ref "USB1") (pin "6") (pinfunction "EH_6") (pintype "input+no_connect"))
    )
    (net (code "101") (name "unconnected-(USB1-ID-Pad4)") (class "Default")
      (node (ref "USB1") (pin "4") (pinfunction "ID_4") (pintype "input+no_connect"))
    )
  )
)
